# SI5324_CLK_RECOVERY.net
KiCad netlist of a schematic drawn in Altium Designer
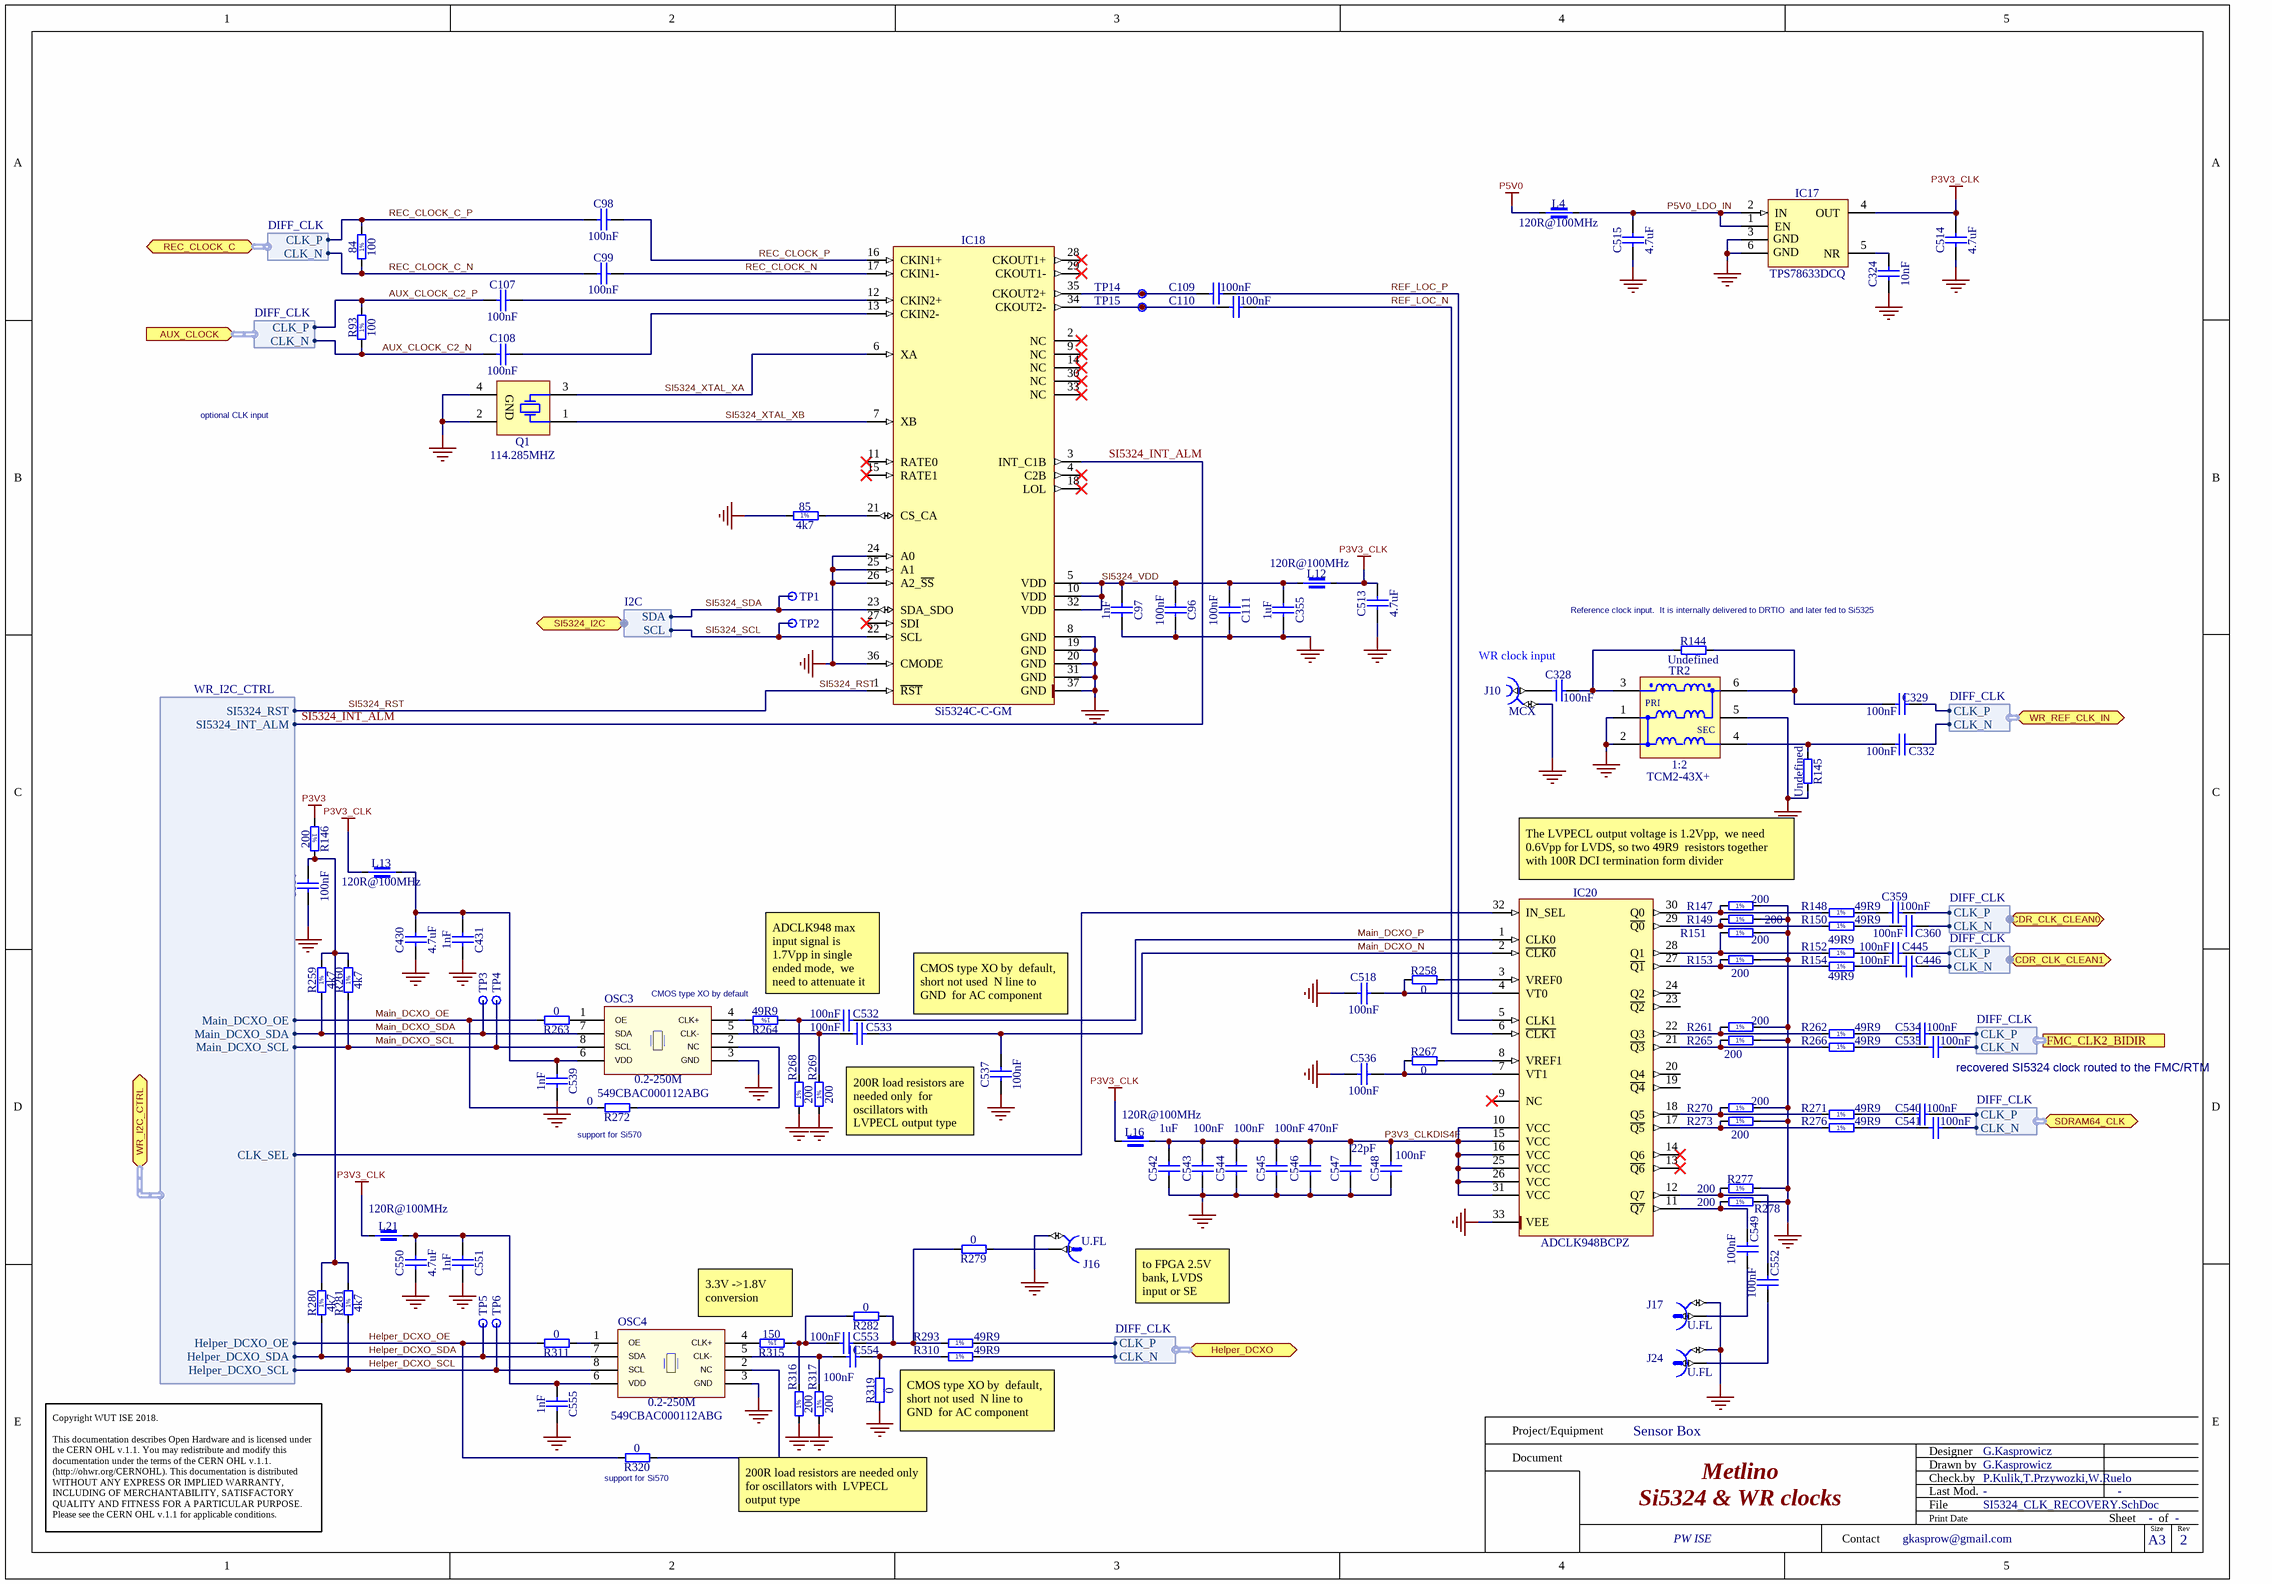
[diagram p0: SI5324_CLK_RECOVERY.SchDoc]

(export (version "E")
  (design (tool "Eeschema 10.0.6"))
  (components
    (comp (ref "84")
      (value "100")
      (footprint "RESC1005X40N")
      (description "Resistor - 1%")
      (fields
        (field (name "MANUFACTURER PART NUMBER") "R0402_100R_1%_0.0625W_100PPM")
        (field (name "MANUFACTURER") "GENERIC")
        (field (name "AUTHOR") "CERN DEM JLC")
      )
      (libsource (lib "Resistors") (part "Resistor - 1%"))
    )
    (comp (ref "85")
      (value "4k7")
      (footprint "RESC1005X40N")
      (description "Resistor - 1%")
      (fields
        (field (name "MANUFACTURER PART NUMBER") "R0402_4K7_1%_0.0625W_100PPM")
        (field (name "MANUFACTURER") "GENERIC")
        (field (name "AUTHOR") "CERN DEM JLC")
      )
      (libsource (lib "Resistors") (part "Resistor - 1%"))
    )
    (comp (ref "C96")
      (value "100nF")
      (footprint "CAPC0603X33N")
      (description "Non-polarised capacitor")
      (fields
        (field (name "MANUFACTURER PART NUMBER") "CC0201_100NF_6.3V_10%_X5R")
        (field (name "MANUFACTURER") "GENERIC")
        (field (name "AUTHOR") "CERN DEM JLC")
      )
      (libsource (lib "Capacitors") (part "Capacitor - non polarized"))
    )
    (comp (ref "C97")
      (value "1nF")
      (footprint "CAPC0603X33N")
      (description "Non-polarised capacitor")
      (fields
        (field (name "MANUFACTURER PART NUMBER") "CC0201_1NF_16V_10%_X5R")
        (field (name "MANUFACTURER") "GENERIC")
        (field (name "AUTHOR") "CERN DEM JLC")
      )
      (libsource (lib "Capacitors") (part "Capacitor - non polarized"))
    )
    (comp (ref "C98")
      (value "100nF")
      (footprint "CAPC0603X33N")
      (description "Non-polarised capacitor")
      (fields
        (field (name "MANUFACTURER PART NUMBER") "CC0201_100NF_6.3V_10%_X5R")
        (field (name "MANUFACTURER") "GENERIC")
        (field (name "AUTHOR") "CERN DEM JLC")
      )
      (libsource (lib "Capacitors") (part "Capacitor - non polarized"))
    )
    (comp (ref "C99")
      (value "100nF")
      (footprint "CAPC0603X33N")
      (description "Non-polarised capacitor")
      (fields
        (field (name "MANUFACTURER PART NUMBER") "CC0201_100NF_6.3V_10%_X5R")
        (field (name "MANUFACTURER") "GENERIC")
        (field (name "AUTHOR") "CERN DEM JLC")
      )
      (libsource (lib "Capacitors") (part "Capacitor - non polarized"))
    )
    (comp (ref "C107")
      (value "100nF")
      (footprint "CAPC0603X33N")
      (description "Non-polarised capacitor")
      (fields
        (field (name "MANUFACTURER PART NUMBER") "CC0201_100NF_6.3V_10%_X5R")
        (field (name "MANUFACTURER") "GENERIC")
        (field (name "AUTHOR") "CERN DEM JLC")
      )
      (libsource (lib "Capacitors") (part "Capacitor - non polarized"))
    )
    (comp (ref "C108")
      (value "100nF")
      (footprint "CAPC0603X33N")
      (description "Non-polarised capacitor")
      (fields
        (field (name "MANUFACTURER PART NUMBER") "CC0201_100NF_6.3V_10%_X5R")
        (field (name "MANUFACTURER") "GENERIC")
        (field (name "AUTHOR") "CERN DEM JLC")
      )
      (libsource (lib "Capacitors") (part "Capacitor - non polarized"))
    )
    (comp (ref "C109")
      (value "100nF")
      (footprint "CAPC1005X55N")
      (description "Non-polarised capacitor")
      (fields
        (field (name "MANUFACTURER PART NUMBER") "CC0402_100NF_16V_10%_X5R")
        (field (name "MANUFACTURER") "GENERIC")
        (field (name "AUTHOR") "CERN DEM JLC")
      )
      (libsource (lib "Capacitors") (part "Capacitor - non polarized"))
    )
    (comp (ref "C110")
      (value "100nF")
      (footprint "CAPC1005X55N")
      (description "Non-polarised capacitor")
      (fields
        (field (name "MANUFACTURER PART NUMBER") "CC0402_100NF_16V_10%_X5R")
        (field (name "MANUFACTURER") "GENERIC")
        (field (name "AUTHOR") "CERN DEM JLC")
      )
      (libsource (lib "Capacitors") (part "Capacitor - non polarized"))
    )
    (comp (ref "C111")
      (value "100nF")
      (footprint "CAPC0603X33N")
      (description "Non-polarised capacitor")
      (fields
        (field (name "MANUFACTURER PART NUMBER") "CC0201_100NF_6.3V_10%_X5R")
        (field (name "MANUFACTURER") "GENERIC")
        (field (name "AUTHOR") "CERN DEM JLC")
      )
      (libsource (lib "Capacitors") (part "Capacitor - non polarized"))
    )
    (comp (ref "C324")
      (value "10nF")
      (footprint "CAPC1608X87N")
      (description "Non-polarised capacitor")
      (fields
        (field (name "PART NUMBER") "CC0603_10NF_50V_5%_C0G")
        (field (name "VOLTAGE") "50V")
        (field (name "AUTHOR") "CERN DEM JLC")
      )
      (libsource (lib "Capacitors") (part "Capacitor - non polarized"))
    )
    (comp (ref "C328")
      (value "100nF")
      (footprint "CAPC1005X55N")
      (description "Non-polarised capacitor")
      (fields
        (field (name "MANUFACTURER PART NUMBER") "CC0402_100NF_16V_10%_X5R")
        (field (name "MANUFACTURER") "GENERIC")
        (field (name "AUTHOR") "CERN DEM JLC")
      )
      (libsource (lib "Capacitors") (part "Capacitor - non polarized"))
    )
    (comp (ref "C329")
      (value "100nF")
      (footprint "CAPC1005X55N")
      (description "Non-polarised capacitor")
      (fields
        (field (name "MANUFACTURER PART NUMBER") "CC0402_100NF_16V_10%_X5R")
        (field (name "MANUFACTURER") "GENERIC")
        (field (name "AUTHOR") "CERN DEM JLC")
      )
      (libsource (lib "Capacitors") (part "Capacitor - non polarized"))
    )
    (comp (ref "C332")
      (value "100nF")
      (footprint "CAPC1005X55N")
      (description "Non-polarised capacitor")
      (fields
        (field (name "MANUFACTURER PART NUMBER") "CC0402_100NF_16V_10%_X5R")
        (field (name "MANUFACTURER") "GENERIC")
        (field (name "AUTHOR") "CERN DEM JLC")
      )
      (libsource (lib "Capacitors") (part "Capacitor - non polarized"))
    )
    (comp (ref "C355")
      (value "1uF")
      (footprint "CAPC1005X55N")
      (description "Non-polarised capacitor")
      (fields
        (field (name "MANUFACTURER PART NUMBER") "CC0402_1UF_16V_10%_X5R")
        (field (name "MANUFACTURER") "GENERIC")
        (field (name "AUTHOR") "CERN DEM JLC")
      )
      (libsource (lib "Capacitors") (part "Capacitor - non polarized"))
    )
    (comp (ref "C356")
      (value "100nF")
      (footprint "CAPC0603X33N")
      (description "Non-polarised capacitor")
      (fields
        (field (name "MANUFACTURER PART NUMBER") "CC0201_100NF_6.3V_10%_X5R")
        (field (name "MANUFACTURER") "GENERIC")
        (field (name "AUTHOR") "CERN DEM JLC")
      )
      (libsource (lib "Capacitors") (part "Capacitor - non polarized"))
    )
    (comp (ref "C359")
      (value "100nF")
      (footprint "CAPC0603X33N")
      (description "Non-polarised capacitor")
      (fields
        (field (name "MANUFACTURER PART NUMBER") "CC0201_100NF_6.3V_10%_X5R")
        (field (name "MANUFACTURER") "GENERIC")
        (field (name "AUTHOR") "CERN DEM JLC")
      )
      (libsource (lib "Capacitors") (part "Capacitor - non polarized"))
    )
    (comp (ref "C360")
      (value "100nF")
      (footprint "CAPC0603X33N")
      (description "Non-polarised capacitor")
      (fields
        (field (name "MANUFACTURER PART NUMBER") "CC0201_100NF_6.3V_10%_X5R")
        (field (name "MANUFACTURER") "GENERIC")
        (field (name "AUTHOR") "CERN DEM JLC")
      )
      (libsource (lib "Capacitors") (part "Capacitor - non polarized"))
    )
    (comp (ref "C430")
      (value "4.7uF")
      (footprint "CAPC1608X90N")
      (description "Non-polarised capacitor")
      (fields
        (field (name "MANUFACTURER PART NUMBER") "CC0603_4.7UF_25V_10%_X5R")
        (field (name "MANUFACTURER") "GENERIC")
        (field (name "AUTHOR") "CERN DEM JLC")
      )
      (libsource (lib "Capacitors") (part "Capacitor - non polarized"))
    )
    (comp (ref "C431")
      (value "1nF")
      (footprint "CAPC0603X33N")
      (description "Non-polarised capacitor")
      (fields
        (field (name "MANUFACTURER PART NUMBER") "CC0201_1NF_16V_10%_X5R")
        (field (name "MANUFACTURER") "GENERIC")
        (field (name "AUTHOR") "CERN DEM JLC")
      )
      (libsource (lib "Capacitors") (part "Capacitor - non polarized"))
    )
    (comp (ref "C445")
      (value "100nF")
      (footprint "CAPC0603X33N")
      (description "Non-polarised capacitor")
      (fields
        (field (name "MANUFACTURER PART NUMBER") "CC0201_100NF_6.3V_10%_X5R")
        (field (name "MANUFACTURER") "GENERIC")
        (field (name "AUTHOR") "CERN DEM JLC")
      )
      (libsource (lib "Capacitors") (part "Capacitor - non polarized"))
    )
    (comp (ref "C446")
      (value "100nF")
      (footprint "CAPC0603X33N")
      (description "Non-polarised capacitor")
      (fields
        (field (name "MANUFACTURER PART NUMBER") "CC0201_100NF_6.3V_10%_X5R")
        (field (name "MANUFACTURER") "GENERIC")
        (field (name "AUTHOR") "CERN DEM JLC")
      )
      (libsource (lib "Capacitors") (part "Capacitor - non polarized"))
    )
    (comp (ref "C513")
      (value "4.7uF")
      (footprint "CAPC1608X90N")
      (description "Non-polarised capacitor")
      (fields
        (field (name "MANUFACTURER PART NUMBER") "CC0603_4.7UF_25V_10%_X5R")
        (field (name "MANUFACTURER") "GENERIC")
        (field (name "AUTHOR") "CERN DEM JLC")
      )
      (libsource (lib "Capacitors") (part "Capacitor - non polarized"))
    )
    (comp (ref "C514")
      (value "4.7uF")
      (footprint "CAPC1608X90N")
      (description "Non-polarised capacitor")
      (fields
        (field (name "MANUFACTURER PART NUMBER") "CC0603_4.7UF_25V_10%_X5R")
        (field (name "MANUFACTURER") "GENERIC")
        (field (name "AUTHOR") "CERN DEM JLC")
      )
      (libsource (lib "Capacitors") (part "Capacitor - non polarized"))
    )
    (comp (ref "C515")
      (value "4.7uF")
      (footprint "CAPC1608X90N")
      (description "Non-polarised capacitor")
      (fields
        (field (name "MANUFACTURER PART NUMBER") "CC0603_4.7UF_25V_10%_X5R")
        (field (name "MANUFACTURER") "GENERIC")
        (field (name "AUTHOR") "CERN DEM JLC")
      )
      (libsource (lib "Capacitors") (part "Capacitor - non polarized"))
    )
    (comp (ref "C518")
      (value "100nF")
      (footprint "CAPC0603X33N")
      (description "Non-polarised capacitor")
      (fields
        (field (name "MANUFACTURER PART NUMBER") "CC0201_100NF_6.3V_10%_X5R")
        (field (name "MANUFACTURER") "GENERIC")
        (field (name "AUTHOR") "CERN DEM JLC")
      )
      (libsource (lib "Capacitors") (part "Capacitor - non polarized"))
    )
    (comp (ref "C532")
      (value "100nF")
      (footprint "CAPC1005X55N")
      (description "Non-polarised capacitor")
      (fields
        (field (name "MANUFACTURER PART NUMBER") "CC0402_100NF_16V_10%_X5R")
        (field (name "MANUFACTURER") "GENERIC")
        (field (name "AUTHOR") "CERN DEM JLC")
      )
      (libsource (lib "Capacitors") (part "Capacitor - non polarized"))
    )
    (comp (ref "C533")
      (value "100nF")
      (footprint "CAPC1005X55N")
      (description "Non-polarised capacitor")
      (fields
        (field (name "MANUFACTURER PART NUMBER") "CC0402_100NF_16V_10%_X5R")
        (field (name "MANUFACTURER") "GENERIC")
        (field (name "AUTHOR") "CERN DEM JLC")
      )
      (libsource (lib "Capacitors") (part "Capacitor - non polarized"))
    )
    (comp (ref "C534")
      (value "100nF")
      (footprint "CAPC0603X33N")
      (description "Non-polarised capacitor")
      (fields
        (field (name "MANUFACTURER PART NUMBER") "CC0201_100NF_6.3V_10%_X5R")
        (field (name "MANUFACTURER") "GENERIC")
        (field (name "AUTHOR") "CERN DEM JLC")
      )
      (libsource (lib "Capacitors") (part "Capacitor - non polarized"))
    )
    (comp (ref "C535")
      (value "100nF")
      (footprint "CAPC0603X33N")
      (description "Non-polarised capacitor")
      (fields
        (field (name "MANUFACTURER PART NUMBER") "CC0201_100NF_6.3V_10%_X5R")
        (field (name "MANUFACTURER") "GENERIC")
        (field (name "AUTHOR") "CERN DEM JLC")
      )
      (libsource (lib "Capacitors") (part "Capacitor - non polarized"))
    )
    (comp (ref "C536")
      (value "100nF")
      (footprint "CAPC0603X33N")
      (description "Non-polarised capacitor")
      (fields
        (field (name "MANUFACTURER PART NUMBER") "CC0201_100NF_6.3V_10%_X5R")
        (field (name "MANUFACTURER") "GENERIC")
        (field (name "AUTHOR") "CERN DEM JLC")
      )
      (libsource (lib "Capacitors") (part "Capacitor - non polarized"))
    )
    (comp (ref "C537")
      (value "100nF")
      (footprint "CAPC0603X33N")
      (description "Non-polarised capacitor")
      (fields
        (field (name "MANUFACTURER PART NUMBER") "CC0201_100NF_6.3V_10%_X5R")
        (field (name "MANUFACTURER") "GENERIC")
        (field (name "AUTHOR") "CERN DEM JLC")
      )
      (libsource (lib "Capacitors") (part "Capacitor - non polarized"))
    )
    (comp (ref "C539")
      (value "1nF")
      (footprint "CAPC0603X33N")
      (description "Non-polarised capacitor")
      (fields
        (field (name "MANUFACTURER PART NUMBER") "CC0201_1NF_16V_10%_X5R")
        (field (name "MANUFACTURER") "GENERIC")
        (field (name "AUTHOR") "CERN DEM JLC")
      )
      (libsource (lib "Capacitors") (part "Capacitor - non polarized"))
    )
    (comp (ref "C540")
      (value "100nF")
      (footprint "CAPC0603X33N")
      (description "Non-polarised capacitor")
      (fields
        (field (name "MANUFACTURER PART NUMBER") "CC0201_100NF_6.3V_10%_X5R")
        (field (name "MANUFACTURER") "GENERIC")
        (field (name "AUTHOR") "CERN DEM JLC")
      )
      (libsource (lib "Capacitors") (part "Capacitor - non polarized"))
    )
    (comp (ref "C541")
      (value "100nF")
      (footprint "CAPC0603X33N")
      (description "Non-polarised capacitor")
      (fields
        (field (name "MANUFACTURER PART NUMBER") "CC0201_100NF_6.3V_10%_X5R")
        (field (name "MANUFACTURER") "GENERIC")
        (field (name "AUTHOR") "CERN DEM JLC")
      )
      (libsource (lib "Capacitors") (part "Capacitor - non polarized"))
    )
    (comp (ref "C542")
      (value "1uF")
      (footprint "CAPC1005X55N")
      (description "Non-polarised capacitor")
      (fields
        (field (name "MANUFACTURER PART NUMBER") "CC0402_1UF_16V_10%_X5R")
        (field (name "MANUFACTURER") "GENERIC")
        (field (name "AUTHOR") "CERN DEM JLC")
      )
      (libsource (lib "Capacitors") (part "Capacitor - non polarized"))
    )
    (comp (ref "C543")
      (value "100nF")
      (footprint "CAPC0603X33N")
      (description "Non-polarised capacitor")
      (fields
        (field (name "MANUFACTURER PART NUMBER") "CC0201_100NF_6.3V_10%_X5R")
        (field (name "MANUFACTURER") "GENERIC")
        (field (name "AUTHOR") "CERN DEM JLC")
      )
      (libsource (lib "Capacitors") (part "Capacitor - non polarized"))
    )
    (comp (ref "C544")
      (value "100nF")
      (footprint "CAPC0603X33N")
      (description "Non-polarised capacitor")
      (fields
        (field (name "MANUFACTURER PART NUMBER") "CC0201_100NF_6.3V_10%_X5R")
        (field (name "MANUFACTURER") "GENERIC")
        (field (name "AUTHOR") "CERN DEM JLC")
      )
      (libsource (lib "Capacitors") (part "Capacitor - non polarized"))
    )
    (comp (ref "C545")
      (value "100nF")
      (footprint "CAPC0603X33N")
      (description "Non-polarised capacitor")
      (fields
        (field (name "MANUFACTURER PART NUMBER") "CC0201_100NF_6.3V_10%_X5R")
        (field (name "MANUFACTURER") "GENERIC")
        (field (name "AUTHOR") "CERN DEM JLC")
      )
      (libsource (lib "Capacitors") (part "Capacitor - non polarized"))
    )
    (comp (ref "C546")
      (value "470nF")
      (footprint "CAPC1005X55N")
      (description "Non-polarised capacitor")
      (fields
        (field (name "MANUFACTURER PART NUMBER") "CC0402_470NF_16V_10%_X5R")
        (field (name "MANUFACTURER") "GENERIC")
        (field (name "AUTHOR") "CERN DEM JLC")
      )
      (libsource (lib "Capacitors") (part "Capacitor - non polarized"))
    )
    (comp (ref "C547")
      (value "22pF")
      (footprint "CAPC1005X55N")
      (description "Non-polarised capacitor")
      (fields
        (field (name "MANUFACTURER PART NUMBER") "CC0402_22PF_50V_5%_C0G")
        (field (name "MANUFACTURER") "GENERIC")
        (field (name "AUTHOR") "CERN DEM JLC")
      )
      (libsource (lib "Capacitors") (part "Capacitor - non polarized"))
    )
    (comp (ref "C548")
      (value "100nF")
      (footprint "CAPC0603X33N")
      (description "Non-polarised capacitor")
      (fields
        (field (name "MANUFACTURER PART NUMBER") "CC0201_100NF_6.3V_10%_X5R")
        (field (name "MANUFACTURER") "GENERIC")
        (field (name "AUTHOR") "CERN DEM JLC")
      )
      (libsource (lib "Capacitors") (part "Capacitor - non polarized"))
    )
    (comp (ref "C549")
      (value "100nF")
      (footprint "CAPC0603X33N")
      (description "Non-polarised capacitor")
      (fields
        (field (name "MANUFACTURER PART NUMBER") "CC0201_100NF_6.3V_10%_X5R")
        (field (name "MANUFACTURER") "GENERIC")
        (field (name "AUTHOR") "CERN DEM JLC")
      )
      (libsource (lib "Capacitors") (part "Capacitor - non polarized"))
    )
    (comp (ref "C550")
      (value "4.7uF")
      (footprint "CAPC1608X90N")
      (description "Non-polarised capacitor")
      (fields
        (field (name "MANUFACTURER PART NUMBER") "CC0603_4.7UF_25V_10%_X5R")
        (field (name "MANUFACTURER") "GENERIC")
        (field (name "AUTHOR") "CERN DEM JLC")
      )
      (libsource (lib "Capacitors") (part "Capacitor - non polarized"))
    )
    (comp (ref "C551")
      (value "1nF")
      (footprint "CAPC0603X33N")
      (description "Non-polarised capacitor")
      (fields
        (field (name "MANUFACTURER PART NUMBER") "CC0201_1NF_16V_10%_X5R")
        (field (name "MANUFACTURER") "GENERIC")
        (field (name "AUTHOR") "CERN DEM JLC")
      )
      (libsource (lib "Capacitors") (part "Capacitor - non polarized"))
    )
    (comp (ref "C552")
      (value "100nF")
      (footprint "CAPC0603X33N")
      (description "Non-polarised capacitor")
      (fields
        (field (name "MANUFACTURER PART NUMBER") "CC0201_100NF_6.3V_10%_X5R")
        (field (name "MANUFACTURER") "GENERIC")
        (field (name "AUTHOR") "CERN DEM JLC")
      )
      (libsource (lib "Capacitors") (part "Capacitor - non polarized"))
    )
    (comp (ref "C553")
      (value "100nF")
      (footprint "CAPC1005X55N")
      (description "Non-polarised capacitor")
      (fields
        (field (name "MANUFACTURER PART NUMBER") "CC0402_100NF_16V_10%_X5R")
        (field (name "MANUFACTURER") "GENERIC")
        (field (name "AUTHOR") "CERN DEM JLC")
      )
      (libsource (lib "Capacitors") (part "Capacitor - non polarized"))
    )
    (comp (ref "C554")
      (value "100nF")
      (footprint "CAPC1005X55N")
      (description "Non-polarised capacitor")
      (fields
        (field (name "MANUFACTURER PART NUMBER") "CC0402_100NF_16V_10%_X5R")
        (field (name "MANUFACTURER") "GENERIC")
        (field (name "AUTHOR") "CERN DEM JLC")
      )
      (libsource (lib "Capacitors") (part "Capacitor - non polarized"))
    )
    (comp (ref "C555")
      (value "1nF")
      (footprint "CAPC0603X33N")
      (description "Non-polarised capacitor")
      (fields
        (field (name "MANUFACTURER PART NUMBER") "CC0201_1NF_16V_10%_X5R")
        (field (name "MANUFACTURER") "GENERIC")
        (field (name "AUTHOR") "CERN DEM JLC")
      )
      (libsource (lib "Capacitors") (part "Capacitor - non polarized"))
    )
    (comp (ref "IC17")
      (value "TPS78633DCQ")
      (footprint "SOT127P700X180-6N")
      (description "Ultralow-Noise, High-PSRR, Fast, RF, 1.5A Low-Dropout Linear Regulator")
      (fields (field (name "MANUFACTURER") "TEXAS INSTRUMENTS") (field (name "AUTHOR") "CERN DEM JMW"))
      (libsource (lib "ICs And Semiconductors") (part "TPS786xxDCQ"))
    )
    (comp (ref "IC18")
      (value "Si5324C-C-GM")
      (footprint "QFN50P600X600X90-37N-S425")
      (description "Any Frequency Precision Clock Multiplier/Jitter Attenuator")
      (fields (field (name "MANUFACTURER") "SILICON LABS") (field (name "AUTHOR") "CERN DEM JLC"))
      (libsource (lib "ICs And Semiconductors") (part "Si5324"))
    )
    (comp (ref "IC20")
      (value "ADCLK948BCPZ")
      (footprint "QFN50P500X500X80-33N-S285")
      (description "Two Selectable Inputs, 8 LVPECL Outputs, SiGe Clock Fanout Buffer")
      (fields (field (name "MANUFACTURER") "ANALOG DEVICES") (field (name "AUTHOR") "CERN DEM MR"))
      (libsource (lib "ICs And Semiconductors") (part "ADCLK948"))
    )
    (comp (ref "J10")
      (value "MCX")
      (footprint "AMPHENOL_ARF2521-ND")
      (fields
        (field (name "PART NUMBER") "AMPHENOL_ARF2521-ND")
        (field (name "MANUFACTURER") "AMPHENOL")
        (field (name "AUTHOR") "GK")
      )
      (libsource (lib "LIBRARY_SCH") (part "CON_MCX"))
    )
    (comp (ref "J16")
      (value "U.FL")
      (footprint "HIROSE_U.FL-R-SMT-1(10)")
      (fields
        (field (name "MANUFACTURER PART NUMBER") "U.FL-R-SMT-1(10)")
        (field (name "MANUFACTURER") "HIROSE (HRS)")
        (field (name "PART NUMBER") "HIROSE_U.FL-R-SMT-1(10)")
        (field (name "AUTHOR") "CERN DEM JLC")
      )
      (libsource (lib "") (part "Coax_1Male_1Shield_1"))
    )
    (comp (ref "J17")
      (value "U.FL")
      (footprint "HIROSE_U.FL-R-SMT-1(10)")
      (fields
        (field (name "MANUFACTURER PART NUMBER") "U.FL-R-SMT-1(10)")
        (field (name "MANUFACTURER") "HIROSE (HRS)")
        (field (name "PART NUMBER") "HIROSE_U.FL-R-SMT-1(10)")
        (field (name "AUTHOR") "CERN DEM JLC")
      )
      (libsource (lib "Connectors") (part "Coax_1Male_1Shield"))
    )
    (comp (ref "J24")
      (value "U.FL")
      (footprint "HIROSE_U.FL-R-SMT-1(10)")
      (fields
        (field (name "MANUFACTURER PART NUMBER") "U.FL-R-SMT-1(10)")
        (field (name "MANUFACTURER") "HIROSE (HRS)")
        (field (name "PART NUMBER") "HIROSE_U.FL-R-SMT-1(10)")
        (field (name "AUTHOR") "CERN DEM JLC")
      )
      (libsource (lib "Connectors") (part "Coax_1Male_1Shield"))
    )
    (comp (ref "L4")
      (value "120R@100MHz")
      (footprint "INDC1608X95N")
      (fields
        (field (name "MANUFACTURER PART NUMBER") "BLM18PG121SN1D")
        (field (name "MANUFACTURER") "MURATA")
        (field (name "PART NUMBER") "IND0603_MURATA_BLM18PG121SN1D")
        (field (name "AUTHOR") "CERN DEM BC")
      )
      (libsource (lib "Inductors & Transformers") (part "Ferrite Bead"))
    )
    (comp (ref "L12")
      (value "120R@100MHz")
      (footprint "INDC1608X95N")
      (fields
        (field (name "MANUFACTURER PART NUMBER") "BLM18PG121SN1D")
        (field (name "MANUFACTURER") "MURATA")
        (field (name "PART NUMBER") "IND0603_MURATA_BLM18PG121SN1D")
        (field (name "AUTHOR") "CERN DEM BC")
      )
      (libsource (lib "") (part "Ferrite Bead_1"))
    )
    (comp (ref "L13")
      (value "120R@100MHz")
      (footprint "INDC1608X95N")
      (fields
        (field (name "MANUFACTURER PART NUMBER") "BLM18PG121SN1D")
        (field (name "MANUFACTURER") "MURATA")
        (field (name "PART NUMBER") "IND0603_MURATA_BLM18PG121SN1D")
        (field (name "AUTHOR") "CERN DEM BC")
      )
      (libsource (lib "Inductors & Transformers") (part "Ferrite Bead"))
    )
    (comp (ref "L16")
      (value "120R@100MHz")
      (footprint "INDC1608X95N")
      (fields
        (field (name "MANUFACTURER PART NUMBER") "BLM18PG121SN1D")
        (field (name "MANUFACTURER") "MURATA")
        (field (name "PART NUMBER") "IND0603_MURATA_BLM18PG121SN1D")
        (field (name "AUTHOR") "CERN DEM BC")
      )
      (libsource (lib "Inductors & Transformers") (part "Ferrite Bead"))
    )
    (comp (ref "L21")
      (value "120R@100MHz")
      (footprint "INDC1608X95N")
      (fields
        (field (name "MANUFACTURER PART NUMBER") "BLM18PG121SN1D")
        (field (name "MANUFACTURER") "MURATA")
        (field (name "PART NUMBER") "IND0603_MURATA_BLM18PG121SN1D")
        (field (name "AUTHOR") "CERN DEM BC")
      )
      (libsource (lib "Inductors & Transformers") (part "Ferrite Bead"))
    )
    (comp (ref "OSC3")
      (value "0.2-250M")
      (footprint "OSC_SILICON-LAB_SI549")
      (fields
        (field (name "MANUFACTURER PART NUMBER") "549CBAC000112ABG")
        (field (name "MANUFACTURER") "Silabs")
        (field (name "PART NUMBER") "OSC_0.2_250M_SILICON-LAB_549CBAC000112ABG")
      )
      (libsource (lib "LIBRARY_SCH") (part "OSC_SILICON-LAB_SI549"))
    )
    (comp (ref "OSC4")
      (value "0.2-250M")
      (footprint "OSC_SILICON-LAB_SI549")
      (fields
        (field (name "MANUFACTURER PART NUMBER") "549CBAC000112ABG")
        (field (name "MANUFACTURER") "Silabs")
        (field (name "PART NUMBER") "OSC_0.2_250M_SILICON-LAB_549CBAC000112ABG")
      )
      (libsource (lib "LIBRARY_SCH") (part "OSC_SILICON-LAB_SI549"))
    )
    (comp (ref "Q1")
      (value "114.285MHZ")
      (footprint "XTAL_CONNOR_CS")
      (description "Crystal 4 pins 1=XTAL Control 2=GND3=XTAL 4=GND")
      (fields
        (field (name "MANUFACTURER PART NUMBER") "CS-023-114.285M")
        (field (name "MANUFACTURER") "CONNOR-WINFIELD")
        (field (name "AUTHOR") "CERN DEM JLC")
      )
      (libsource (lib "ICs And Semiconductors") (part "Quartz Crystal 1X 2GND 3X 4GND"))
    )
    (comp (ref "R93")
      (value "100")
      (footprint "RESC1005X40N")
      (description "Resistor - 1%")
      (fields
        (field (name "MANUFACTURER PART NUMBER") "R0402_100R_1%_0.0625W_100PPM")
        (field (name "MANUFACTURER") "GENERIC")
        (field (name "AUTHOR") "CERN DEM JLC")
      )
      (libsource (lib "Resistors") (part "Resistor - 1%"))
    )
    (comp (ref "R144")
      (value "Undefined")
      (footprint "RESC1005X40N")
      (description "Resistor")
      (fields
        (field (name "MANUFACTURER PART NUMBER") "R0402_NO-VALUE")
        (field (name "AUTHOR") "CERN DEM JLC")
      )
      (libsource (lib "Resistors") (part "Resistor"))
    )
    (comp (ref "R145")
      (value "Undefined")
      (footprint "RESC1005X40N")
      (description "Resistor")
      (fields
        (field (name "MANUFACTURER PART NUMBER") "R0402_NO-VALUE")
        (field (name "AUTHOR") "CERN DEM JLC")
      )
      (libsource (lib "Resistors") (part "Resistor"))
    )
    (comp (ref "R146")
      (value "200")
      (footprint "RESC1005X40N")
      (description "Resistor - 1%")
      (fields
        (field (name "MANUFACTURER PART NUMBER") "R0402_200R_1%_0.0625W_100PPM")
        (field (name "MANUFACTURER") "GENERIC")
        (field (name "AUTHOR") "CERN DEM JLC")
      )
      (libsource (lib "Resistors") (part "Resistor - 1%"))
    )
    (comp (ref "R147")
      (value "200")
      (footprint "RESC1005X40N")
      (description "Resistor - 1%")
      (fields
        (field (name "MANUFACTURER PART NUMBER") "R0402_200R_1%_0.0625W_100PPM")
        (field (name "MANUFACTURER") "GENERIC")
        (field (name "AUTHOR") "CERN DEM JLC")
      )
      (libsource (lib "Resistors") (part "Resistor - 1%"))
    )
    (comp (ref "R148")
      (value "49R9")
      (footprint "RESC1005X40N")
      (description "Resistor - 1%")
      (fields
        (field (name "MANUFACTURER PART NUMBER") "R0402_49R9_1%_0.0625W_100PPM")
        (field (name "MANUFACTURER") "GENERIC")
        (field (name "AUTHOR") "CERN DEM JLC")
      )
      (libsource (lib "Resistors") (part "Resistor - 1%"))
    )
    (comp (ref "R149")
      (value "200")
      (footprint "RESC1005X40N")
      (description "Resistor - 1%")
      (fields
        (field (name "MANUFACTURER PART NUMBER") "R0402_200R_1%_0.0625W_100PPM")
        (field (name "MANUFACTURER") "GENERIC")
        (field (name "AUTHOR") "CERN DEM JLC")
      )
      (libsource (lib "Resistors") (part "Resistor - 1%"))
    )
    (comp (ref "R150")
      (value "49R9")
      (footprint "RESC1005X40N")
      (description "Resistor - 1%")
      (fields
        (field (name "MANUFACTURER PART NUMBER") "R0402_49R9_1%_0.0625W_100PPM")
        (field (name "MANUFACTURER") "GENERIC")
        (field (name "AUTHOR") "CERN DEM JLC")
      )
      (libsource (lib "Resistors") (part "Resistor - 1%"))
    )
    (comp (ref "R151")
      (value "200")
      (footprint "RESC1005X40N")
      (description "Resistor - 1%")
      (fields
        (field (name "MANUFACTURER PART NUMBER") "R0402_200R_1%_0.0625W_100PPM")
        (field (name "MANUFACTURER") "GENERIC")
        (field (name "AUTHOR") "CERN DEM JLC")
      )
      (libsource (lib "Resistors") (part "Resistor - 1%"))
    )
    (comp (ref "R152")
      (value "49R9")
      (footprint "RESC1005X40N")
      (description "Resistor - 1%")
      (fields
        (field (name "MANUFACTURER PART NUMBER") "R0402_49R9_1%_0.0625W_100PPM")
        (field (name "MANUFACTURER") "GENERIC")
        (field (name "AUTHOR") "CERN DEM JLC")
      )
      (libsource (lib "Resistors") (part "Resistor - 1%"))
    )
    (comp (ref "R153")
      (value "200")
      (footprint "RESC1005X40N")
      (description "Resistor - 1%")
      (fields
        (field (name "MANUFACTURER PART NUMBER") "R0402_200R_1%_0.0625W_100PPM")
        (field (name "MANUFACTURER") "GENERIC")
        (field (name "AUTHOR") "CERN DEM JLC")
      )
      (libsource (lib "Resistors") (part "Resistor - 1%"))
    )
    (comp (ref "R154")
      (value "49R9")
      (footprint "RESC1005X40N")
      (description "Resistor - 1%")
      (fields
        (field (name "MANUFACTURER PART NUMBER") "R0402_49R9_1%_0.0625W_100PPM")
        (field (name "MANUFACTURER") "GENERIC")
        (field (name "AUTHOR") "CERN DEM JLC")
      )
      (libsource (lib "Resistors") (part "Resistor - 1%"))
    )
    (comp (ref "R258")
      (value "0")
      (footprint "RESC1005X40N")
      (description "Resistor")
      (fields
        (field (name "MANUFACTURER PART NUMBER") "R0402_0R_JUMPER")
        (field (name "MANUFACTURER") "GENERIC")
        (field (name "AUTHOR") "CERN DEM JLC")
      )
      (libsource (lib "Resistors") (part "Resistor"))
    )
    (comp (ref "R259")
      (value "4k7")
      (footprint "RESC1005X40N")
      (description "Resistor - 1%")
      (fields
        (field (name "MANUFACTURER PART NUMBER") "R0402_4K7_1%_0.0625W_100PPM")
        (field (name "MANUFACTURER") "GENERIC")
        (field (name "AUTHOR") "CERN DEM JLC")
      )
      (libsource (lib "Resistors") (part "Resistor - 1%"))
    )
    (comp (ref "R260")
      (value "4k7")
      (footprint "RESC1005X40N")
      (description "Resistor - 1%")
      (fields
        (field (name "MANUFACTURER PART NUMBER") "R0402_4K7_1%_0.0625W_100PPM")
        (field (name "MANUFACTURER") "GENERIC")
        (field (name "AUTHOR") "CERN DEM JLC")
      )
      (libsource (lib "Resistors") (part "Resistor - 1%"))
    )
    (comp (ref "R261")
      (value "200")
      (footprint "RESC1005X40N")
      (description "Resistor - 1%")
      (fields
        (field (name "MANUFACTURER PART NUMBER") "R0402_200R_1%_0.0625W_100PPM")
        (field (name "MANUFACTURER") "GENERIC")
        (field (name "AUTHOR") "CERN DEM JLC")
      )
      (libsource (lib "Resistors") (part "Resistor - 1%"))
    )
    (comp (ref "R262")
      (value "49R9")
      (footprint "RESC1005X40N")
      (description "Resistor - 1%")
      (fields
        (field (name "MANUFACTURER PART NUMBER") "R0402_49R9_1%_0.0625W_100PPM")
        (field (name "MANUFACTURER") "GENERIC")
        (field (name "AUTHOR") "CERN DEM JLC")
      )
      (libsource (lib "Resistors") (part "Resistor - 1%"))
    )
    (comp (ref "R263")
      (value "0")
      (footprint "RESC1005X40N")
      (description "Resistor")
      (fields
        (field (name "MANUFACTURER PART NUMBER") "R0402_0R_JUMPER")
        (field (name "MANUFACTURER") "GENERIC")
        (field (name "AUTHOR") "CERN DEM JLC")
      )
      (libsource (lib "Resistors") (part "Resistor"))
    )
    (comp (ref "R264")
      (value "49R9")
      (footprint "RESC1005X40N")
      (description "Resistor - 1%")
      (fields
        (field (name "MANUFACTURER PART NUMBER") "R0402_49R9_1%_0.0625W_100PPM")
        (field (name "MANUFACTURER") "GENERIC")
        (field (name "AUTHOR") "CERN DEM JLC")
      )
      (libsource (lib "Resistors") (part "Resistor - 1%"))
    )
    (comp (ref "R265")
      (value "200")
      (footprint "RESC1005X40N")
      (description "Resistor - 1%")
      (fields
        (field (name "MANUFACTURER PART NUMBER") "R0402_200R_1%_0.0625W_100PPM")
        (field (name "MANUFACTURER") "GENERIC")
        (field (name "AUTHOR") "CERN DEM JLC")
      )
      (libsource (lib "Resistors") (part "Resistor - 1%"))
    )
    (comp (ref "R266")
      (value "49R9")
      (footprint "RESC1005X40N")
      (description "Resistor - 1%")
      (fields
        (field (name "MANUFACTURER PART NUMBER") "R0402_49R9_1%_0.0625W_100PPM")
        (field (name "MANUFACTURER") "GENERIC")
        (field (name "AUTHOR") "CERN DEM JLC")
      )
      (libsource (lib "Resistors") (part "Resistor - 1%"))
    )
    (comp (ref "R267")
      (value "0")
      (footprint "RESC1005X40N")
      (description "Resistor")
      (fields
        (field (name "MANUFACTURER PART NUMBER") "R0402_0R_JUMPER")
        (field (name "MANUFACTURER") "GENERIC")
        (field (name "AUTHOR") "CERN DEM JLC")
      )
      (libsource (lib "Resistors") (part "Resistor"))
    )
    (comp (ref "R268")
      (value "200")
      (footprint "RESC1005X40N")
      (description "Resistor - 1%")
      (fields
        (field (name "MANUFACTURER PART NUMBER") "R0402_200R_1%_0.0625W_100PPM")
        (field (name "MANUFACTURER") "GENERIC")
        (field (name "AUTHOR") "CERN DEM JLC")
      )
      (libsource (lib "Resistors") (part "Resistor - 1%"))
    )
    (comp (ref "R269")
      (value "200")
      (footprint "RESC1005X40N")
      (description "Resistor - 1%")
      (fields
        (field (name "MANUFACTURER PART NUMBER") "R0402_200R_1%_0.0625W_100PPM")
        (field (name "MANUFACTURER") "GENERIC")
        (field (name "AUTHOR") "CERN DEM JLC")
      )
      (libsource (lib "Resistors") (part "Resistor - 1%"))
    )
    (comp (ref "R270")
      (value "200")
      (footprint "RESC1005X40N")
      (description "Resistor - 1%")
      (fields
        (field (name "MANUFACTURER PART NUMBER") "R0402_200R_1%_0.0625W_100PPM")
        (field (name "MANUFACTURER") "GENERIC")
        (field (name "AUTHOR") "CERN DEM JLC")
      )
      (libsource (lib "Resistors") (part "Resistor - 1%"))
    )
    (comp (ref "R271")
      (value "49R9")
      (footprint "RESC1005X40N")
      (description "Resistor - 1%")
      (fields
        (field (name "MANUFACTURER PART NUMBER") "R0402_49R9_1%_0.0625W_100PPM")
        (field (name "MANUFACTURER") "GENERIC")
        (field (name "AUTHOR") "CERN DEM JLC")
      )
      (libsource (lib "Resistors") (part "Resistor - 1%"))
    )
    (comp (ref "R272")
      (value "0")
      (footprint "RESC1005X40N")
      (description "Resistor")
      (fields
        (field (name "MANUFACTURER PART NUMBER") "R0402_0R_JUMPER")
        (field (name "MANUFACTURER") "GENERIC")
        (field (name "AUTHOR") "CERN DEM JLC")
      )
      (libsource (lib "Resistors") (part "Resistor"))
    )
    (comp (ref "R273")
      (value "200")
      (footprint "RESC1005X40N")
      (description "Resistor - 1%")
      (fields
        (field (name "MANUFACTURER PART NUMBER") "R0402_200R_1%_0.0625W_100PPM")
        (field (name "MANUFACTURER") "GENERIC")
        (field (name "AUTHOR") "CERN DEM JLC")
      )
      (libsource (lib "Resistors") (part "Resistor - 1%"))
    )
    (comp (ref "R276")
      (value "49R9")
      (footprint "RESC1005X40N")
      (description "Resistor - 1%")
      (fields
        (field (name "MANUFACTURER PART NUMBER") "R0402_49R9_1%_0.0625W_100PPM")
        (field (name "MANUFACTURER") "GENERIC")
        (field (name "AUTHOR") "CERN DEM JLC")
      )
      (libsource (lib "Resistors") (part "Resistor - 1%"))
    )
    (comp (ref "R277")
      (value "200")
      (footprint "RESC1005X40N")
      (description "Resistor - 1%")
      (fields
        (field (name "MANUFACTURER PART NUMBER") "R0402_200R_1%_0.0625W_100PPM")
        (field (name "MANUFACTURER") "GENERIC")
        (field (name "AUTHOR") "CERN DEM JLC")
      )
      (libsource (lib "Resistors") (part "Resistor - 1%"))
    )
    (comp (ref "R278")
      (value "200")
      (footprint "RESC1005X40N")
      (description "Resistor - 1%")
      (fields
        (field (name "MANUFACTURER PART NUMBER") "R0402_200R_1%_0.0625W_100PPM")
        (field (name "MANUFACTURER") "GENERIC")
        (field (name "AUTHOR") "CERN DEM JLC")
      )
      (libsource (lib "Resistors") (part "Resistor - 1%"))
    )
    (comp (ref "R279")
      (value "0")
      (footprint "RESC1005X40N")
      (description "Resistor")
      (fields
        (field (name "MANUFACTURER PART NUMBER") "R0402_0R_JUMPER")
        (field (name "MANUFACTURER") "GENERIC")
        (field (name "AUTHOR") "CERN DEM JLC")
      )
      (libsource (lib "Resistors") (part "Resistor"))
    )
    (comp (ref "R280")
      (value "4k7")
      (footprint "RESC1005X40N")
      (description "Resistor - 1%")
      (fields
        (field (name "MANUFACTURER PART NUMBER") "R0402_4K7_1%_0.0625W_100PPM")
        (field (name "MANUFACTURER") "GENERIC")
        (field (name "AUTHOR") "CERN DEM JLC")
      )
      (libsource (lib "Resistors") (part "Resistor - 1%"))
    )
    (comp (ref "R281")
      (value "4k7")
      (footprint "RESC1005X40N")
      (description "Resistor - 1%")
      (fields
        (field (name "MANUFACTURER PART NUMBER") "R0402_4K7_1%_0.0625W_100PPM")
        (field (name "MANUFACTURER") "GENERIC")
        (field (name "AUTHOR") "CERN DEM JLC")
      )
      (libsource (lib "Resistors") (part "Resistor - 1%"))
    )
    (comp (ref "R282")
      (value "0")
      (footprint "RESC1005X40N")
      (description "Resistor")
      (fields
        (field (name "MANUFACTURER PART NUMBER") "R0402_0R_JUMPER")
        (field (name "MANUFACTURER") "GENERIC")
        (field (name "AUTHOR") "CERN DEM JLC")
      )
      (libsource (lib "Resistors") (part "Resistor"))
    )
    (comp (ref "R293")
      (value "49R9")
      (footprint "RESC1005X40N")
      (description "Resistor - 1%")
      (fields
        (field (name "MANUFACTURER PART NUMBER") "R0402_49R9_1%_0.0625W_100PPM")
        (field (name "MANUFACTURER") "GENERIC")
        (field (name "AUTHOR") "CERN DEM JLC")
      )
      (libsource (lib "Resistors") (part "Resistor - 1%"))
    )
    (comp (ref "R310")
      (value "49R9")
      (footprint "RESC1005X40N")
      (description "Resistor - 1%")
      (fields
        (field (name "MANUFACTURER PART NUMBER") "R0402_49R9_1%_0.0625W_100PPM")
        (field (name "MANUFACTURER") "GENERIC")
        (field (name "AUTHOR") "CERN DEM JLC")
      )
      (libsource (lib "Resistors") (part "Resistor - 1%"))
    )
    (comp (ref "R311")
      (value "0")
      (footprint "RESC1005X40N")
      (description "Resistor")
      (fields
        (field (name "MANUFACTURER PART NUMBER") "R0402_0R_JUMPER")
        (field (name "MANUFACTURER") "GENERIC")
        (field (name "AUTHOR") "CERN DEM JLC")
      )
      (libsource (lib "Resistors") (part "Resistor"))
    )
    (comp (ref "R315")
      (value "150")
      (footprint "RESC1005X40N")
      (description "Resistor - 1%")
      (fields
        (field (name "MANUFACTURER PART NUMBER") "R0402_150R_1%_0.0625W_100PPM")
        (field (name "MANUFACTURER") "GENERIC")
        (field (name "AUTHOR") "CERN DEM JLC")
      )
      (libsource (lib "Resistors") (part "Resistor - 1%"))
    )
    (comp (ref "R316")
      (value "200")
      (footprint "RESC1005X40N")
      (description "Resistor - 1%")
      (fields
        (field (name "MANUFACTURER PART NUMBER") "R0402_200R_1%_0.0625W_100PPM")
        (field (name "MANUFACTURER") "GENERIC")
        (field (name "AUTHOR") "CERN DEM JLC")
      )
      (libsource (lib "Resistors") (part "Resistor - 1%"))
    )
    (comp (ref "R317")
      (value "200")
      (footprint "RESC1005X40N")
      (description "Resistor - 1%")
      (fields
        (field (name "MANUFACTURER PART NUMBER") "R0402_200R_1%_0.0625W_100PPM")
        (field (name "MANUFACTURER") "GENERIC")
        (field (name "AUTHOR") "CERN DEM JLC")
      )
      (libsource (lib "Resistors") (part "Resistor - 1%"))
    )
    (comp (ref "R319")
      (value "0")
      (footprint "RESC1005X40N")
      (description "Resistor")
      (fields
        (field (name "MANUFACTURER PART NUMBER") "R0402_0R_JUMPER")
        (field (name "MANUFACTURER") "GENERIC")
        (field (name "AUTHOR") "CERN DEM JLC")
      )
      (libsource (lib "Resistors") (part "Resistor"))
    )
    (comp (ref "R320")
      (value "0")
      (footprint "RESC1005X40N")
      (description "Resistor")
      (fields
        (field (name "MANUFACTURER PART NUMBER") "R0402_0R_JUMPER")
        (field (name "MANUFACTURER") "GENERIC")
        (field (name "AUTHOR") "CERN DEM JLC")
      )
      (libsource (lib "Resistors") (part "Resistor"))
    )
    (comp (ref "TP1")
      (value "Test Point")
      (footprint "TPS127")
      (fields (field (name "PART NUMBER") "SMD_PAD_1.27X1.27MM") (field (name "AUTHOR") "CERN DEM JLC"))
      (libsource (lib "Eletro-mechanical") (part "Test Point"))
    )
    (comp (ref "TP2")
      (value "Test Point")
      (footprint "TPS127")
      (fields (field (name "PART NUMBER") "SMD_PAD_1.27X1.27MM") (field (name "AUTHOR") "CERN DEM JLC"))
      (libsource (lib "Eletro-mechanical") (part "Test Point"))
    )
    (comp (ref "TP3")
      (value "Test Point")
      (footprint "TPS127")
      (fields (field (name "PART NUMBER") "SMD_PAD_1.27X1.27MM") (field (name "AUTHOR") "CERN DEM JLC"))
      (libsource (lib "Eletro-mechanical") (part "Test Point"))
    )
    (comp (ref "TP4")
      (value "Test Point")
      (footprint "TPS127")
      (fields (field (name "PART NUMBER") "SMD_PAD_1.27X1.27MM") (field (name "AUTHOR") "CERN DEM JLC"))
      (libsource (lib "Eletro-mechanical") (part "Test Point"))
    )
    (comp (ref "TP5")
      (value "Test Point")
      (footprint "TPS127")
      (fields (field (name "PART NUMBER") "SMD_PAD_1.27X1.27MM") (field (name "AUTHOR") "CERN DEM JLC"))
      (libsource (lib "Eletro-mechanical") (part "Test Point"))
    )
    (comp (ref "TP6")
      (value "Test Point")
      (footprint "TPS127")
      (fields (field (name "PART NUMBER") "SMD_PAD_1.27X1.27MM") (field (name "AUTHOR") "CERN DEM JLC"))
      (libsource (lib "Eletro-mechanical") (part "Test Point"))
    )
    (comp (ref "TP14")
      (value "Test Point")
      (footprint "TPS127")
      (fields (field (name "PART NUMBER") "SMD_PAD_1.27X1.27MM") (field (name "AUTHOR") "CERN DEM JLC"))
      (libsource (lib "Eletro-mechanical") (part "Test Point"))
    )
    (comp (ref "TP15")
      (value "Test Point")
      (footprint "TPS127")
      (fields (field (name "PART NUMBER") "SMD_PAD_1.27X1.27MM") (field (name "AUTHOR") "CERN DEM JLC"))
      (libsource (lib "Eletro-mechanical") (part "Test Point"))
    )
    (comp (ref "TR2")
      (value "1:2")
      (footprint "XFMR_MINI-CIRCUITS_DB1627")
      (description "50 OHMS 10 to 4000 MHz RF Transformer")
      (fields
        (field (name "PART NUMBER") "XFMR_MINI-CIRCUITS_TCM2-43X+")
        (field (name "POWER") "0.4W")
        (field (name "MANUFACTURER PART NUMBER") "TCM2-43X+")
        (field (name "AUTHOR") "CERN DEM BC")
      )
      (libsource (lib "Inductors & Transformers") (part "XFMR_MINI-CIRCUITS_TCM2-43X"))
    )
  )
  (nets
    (net (code "4") (name "/AUX_CLOCK_C2_N") (class "Default")
      (node (ref "C108") (pin "2") (pinfunction "2_2") (pintype "passive"))
      (node (ref "R93") (pin "1") (pinfunction "1_1") (pintype "passive"))
    )
    (net (code "5") (name "/AUX_CLOCK_C2_P") (class "Default")
      (node (ref "C107") (pin "2") (pinfunction "2_2") (pintype "passive"))
      (node (ref "R93") (pin "2") (pinfunction "2_2") (pintype "passive"))
    )
    (net (code "6") (name "/CLK_SEL") (class "Default")
      (node (ref "IC20") (pin "32") (pinfunction "IN_SEL_32") (pintype "input"))
    )
    (net (code "7") (name "/Helper_DCXO_OE") (class "Default")
      (node (ref "R311") (pin "2") (pinfunction "2_2") (pintype "passive"))
      (node (ref "R320") (pin "2") (pinfunction "2_2") (pintype "passive"))
    )
    (net (code "8") (name "/Helper_DCXO_SCL") (class "Default")
      (node (ref "OSC4") (pin "8") (pinfunction "SCL_8") (pintype "passive"))
      (node (ref "R281") (pin "1") (pinfunction "1_1") (pintype "passive"))
      (node (ref "TP6") (pin "1") (pinfunction "1_1") (pintype "bidirectional"))
    )
    (net (code "9") (name "/Helper_DCXO_SDA") (class "Default")
      (node (ref "OSC4") (pin "7") (pinfunction "SDA_7") (pintype "passive"))
      (node (ref "R280") (pin "1") (pinfunction "1_1") (pintype "passive"))
      (node (ref "TP5") (pin "1") (pinfunction "1_1") (pintype "bidirectional"))
    )
    (net (code "10") (name "/Main_DCXO_N") (class "Default")
      (node (ref "C533") (pin "2") (pinfunction "2_2") (pintype "passive"))
      (node (ref "C537") (pin "2") (pinfunction "2_2") (pintype "passive"))
      (node (ref "IC20") (pin "2") (pinfunction "~{CLK0}_2") (pintype "input"))
    )
    (net (code "11") (name "/Main_DCXO_OE") (class "Default")
      (node (ref "R263") (pin "2") (pinfunction "2_2") (pintype "passive"))
      (node (ref "R272") (pin "2") (pinfunction "2_2") (pintype "passive"))
    )
    (net (code "12") (name "/Main_DCXO_P") (class "Default")
      (node (ref "C532") (pin "2") (pinfunction "2_2") (pintype "passive"))
      (node (ref "IC20") (pin "1") (pinfunction "CLK0_1") (pintype "input"))
    )
    (net (code "13") (name "/Main_DCXO_SCL") (class "Default")
      (node (ref "OSC3") (pin "8") (pinfunction "SCL_8") (pintype "passive"))
      (node (ref "R260") (pin "1") (pinfunction "1_1") (pintype "passive"))
      (node (ref "TP4") (pin "1") (pinfunction "1_1") (pintype "bidirectional"))
    )
    (net (code "14") (name "/Main_DCXO_SDA") (class "Default")
      (node (ref "OSC3") (pin "7") (pinfunction "SDA_7") (pintype "passive"))
      (node (ref "R259") (pin "1") (pinfunction "1_1") (pintype "passive"))
      (node (ref "TP3") (pin "1") (pinfunction "1_1") (pintype "bidirectional"))
    )
    (net (code "15") (name "/P3V3_CLKDIS4F") (class "Default")
      (node (ref "C542") (pin "1") (pinfunction "1_1") (pintype "passive"))
      (node (ref "C543") (pin "2") (pinfunction "2_2") (pintype "passive"))
      (node (ref "C544") (pin "2") (pinfunction "2_2") (pintype "passive"))
      (node (ref "C545") (pin "2") (pinfunction "2_2") (pintype "passive"))
      (node (ref "C546") (pin "2") (pinfunction "2_2") (pintype "passive"))
      (node (ref "C547") (pin "2") (pinfunction "2_2") (pintype "passive"))
      (node (ref "C548") (pin "2") (pinfunction "2_2") (pintype "passive"))
      (node (ref "IC20") (pin "10") (pinfunction "VCC_10") (pintype "power_in"))
      (node (ref "IC20") (pin "15") (pinfunction "VCC_15") (pintype "power_in"))
      (node (ref "IC20") (pin "16") (pinfunction "VCC_16") (pintype "power_in"))
      (node (ref "IC20") (pin "25") (pinfunction "VCC_25") (pintype "power_in"))
      (node (ref "IC20") (pin "26") (pinfunction "VCC_26") (pintype "power_in"))
      (node (ref "IC20") (pin "31") (pinfunction "VCC_31") (pintype "power_in"))
      (node (ref "L16") (pin "2") (pinfunction "2_2") (pintype "passive"))
    )
    (net (code "16") (name "/P5V0_LDO_IN") (class "Default")
      (node (ref "C515") (pin "2") (pinfunction "2_2") (pintype "passive"))
      (node (ref "IC17") (pin "1") (pinfunction "EN_1") (pintype "power_in"))
      (node (ref "IC17") (pin "2") (pinfunction "IN_2") (pintype "input"))
      (node (ref "L4") (pin "2") (pinfunction "2_2") (pintype "passive"))
    )
    (net (code "17") (name "/REC_CLOCK_C_N") (class "Default")
      (node (ref "84") (pin "1") (pinfunction "1_1") (pintype "passive"))
      (node (ref "C99") (pin "2") (pinfunction "2_2") (pintype "passive"))
    )
    (net (code "18") (name "/REC_CLOCK_C_P") (class "Default")
      (node (ref "84") (pin "2") (pinfunction "2_2") (pintype "passive"))
      (node (ref "C98") (pin "2") (pinfunction "2_2") (pintype "passive"))
    )
    (net (code "19") (name "/REC_CLOCK_N") (class "Default")
      (node (ref "C99") (pin "1") (pinfunction "1_1") (pintype "passive"))
      (node (ref "IC18") (pin "17") (pinfunction "CKIN1-_17") (pintype "input"))
    )
    (net (code "20") (name "/REC_CLOCK_P") (class "Default")
      (node (ref "C98") (pin "1") (pinfunction "1_1") (pintype "passive"))
      (node (ref "IC18") (pin "16") (pinfunction "CKIN1+_16") (pintype "input"))
    )
    (net (code "21") (name "/REF_LOC_N") (class "Default")
      (node (ref "C110") (pin "2") (pinfunction "2_2") (pintype "passive"))
      (node (ref "IC20") (pin "6") (pinfunction "~{CLK1}_6") (pintype "input"))
    )
    (net (code "22") (name "/REF_LOC_P") (class "Default")
      (node (ref "C109") (pin "2") (pinfunction "2_2") (pintype "passive"))
      (node (ref "IC20") (pin "5") (pinfunction "CLK1_5") (pintype "input"))
    )
    (net (code "23") (name "/SI5324_INT_ALM") (class "Default")
      (node (ref "IC18") (pin "3") (pinfunction "INT_C1B_3") (pintype "output"))
    )
    (net (code "24") (name "/SI5324_RST") (class "Default")
      (node (ref "IC18") (pin "1") (pinfunction "~{RST}_1") (pintype "input"))
    )
    (net (code "25") (name "/SI5324_SCL") (class "Default")
      (node (ref "IC18") (pin "22") (pinfunction "SCL_22") (pintype "input"))
      (node (ref "TP2") (pin "1") (pinfunction "1_1") (pintype "bidirectional"))
    )
    (net (code "26") (name "/SI5324_SDA") (class "Default")
      (node (ref "IC18") (pin "23") (pinfunction "SDA_SDO_23") (pintype "bidirectional"))
      (node (ref "TP1") (pin "1") (pinfunction "1_1") (pintype "bidirectional"))
    )
    (net (code "27") (name "/SI5324_VDD") (class "Default")
      (node (ref "C111") (pin "2") (pinfunction "2_2") (pintype "passive"))
      (node (ref "C355") (pin "1") (pinfunction "1_1") (pintype "passive"))
      (node (ref "C96") (pin "2") (pinfunction "2_2") (pintype "passive"))
      (node (ref "C97") (pin "2") (pinfunction "2_2") (pintype "passive"))
      (node (ref "IC18") (pin "10") (pinfunction "VDD_10") (pintype "power_in"))
      (node (ref "IC18") (pin "32") (pinfunction "VDD_32") (pintype "power_in"))
      (node (ref "IC18") (pin "5") (pinfunction "VDD_5") (pintype "power_in"))
      (node (ref "L12") (pin "2") (pinfunction "2_2") (pintype "passive"))
    )
    (net (code "28") (name "/SI5324_XTAL_XA") (class "Default")
      (node (ref "IC18") (pin "6") (pinfunction "XA_6") (pintype "input"))
      (node (ref "Q1") (pin "3") (pinfunction "X_3") (pintype "passive"))
    )
    (net (code "29") (name "/SI5324_XTAL_XB") (class "Default")
      (node (ref "IC18") (pin "7") (pinfunction "XB_7") (pintype "input"))
      (node (ref "Q1") (pin "1") (pinfunction "X_1") (pintype "passive"))
    )
    (net (code "33") (name "GND") (class "Default")
      (node (ref "85") (pin "1") (pinfunction "1_1") (pintype "passive"))
      (node (ref "C111") (pin "1") (pinfunction "1_1") (pintype "passive"))
      (node (ref "C324") (pin "1") (pinfunction "1_1") (pintype "passive"))
      (node (ref "C355") (pin "2") (pinfunction "2_2") (pintype "passive"))
      (node (ref "C356") (pin "1") (pinfunction "1_1") (pintype "passive"))
      (node (ref "C430") (pin "1") (pinfunction "1_1") (pintype "passive"))
      (node (ref "C431") (pin "1") (pinfunction "1_1") (pintype "passive"))
      (node (ref "C513") (pin "1") (pinfunction "1_1") (pintype "passive"))
      (node (ref "C514") (pin "1") (pinfunction "1_1") (pintype "passive"))
      (node (ref "C515") (pin "1") (pinfunction "1_1") (pintype "passive"))
      (node (ref "C518") (pin "1") (pinfunction "1_1") (pintype "passive"))
      (node (ref "C536") (pin "1") (pinfunction "1_1") (pintype "passive"))
      (node (ref "C537") (pin "1") (pinfunction "1_1") (pintype "passive"))
      (node (ref "C539") (pin "1") (pinfunction "1_1") (pintype "passive"))
      (node (ref "C542") (pin "2") (pinfunction "2_2") (pintype "passive"))
      (node (ref "C543") (pin "1") (pinfunction "1_1") (pintype "passive"))
      (node (ref "C544") (pin "1") (pinfunction "1_1") (pintype "passive"))
      (node (ref "C545") (pin "1") (pinfunction "1_1") (pintype "passive"))
      (node (ref "C546") (pin "1") (pinfunction "1_1") (pintype "passive"))
      (node (ref "C547") (pin "1") (pinfunction "1_1") (pintype "passive"))
      (node (ref "C548") (pin "1") (pinfunction "1_1") (pintype "passive"))
      (node (ref "C550") (pin "1") (pinfunction "1_1") (pintype "passive"))
      (node (ref "C551") (pin "1") (pinfunction "1_1") (pintype "passive"))
      (node (ref "C555") (pin "1") (pinfunction "1_1") (pintype "passive"))
      (node (ref "C96") (pin "1") (pinfunction "1_1") (pintype "passive"))
      (node (ref "C97") (pin "1") (pinfunction "1_1") (pintype "passive"))
      (node (ref "IC17") (pin "3") (pinfunction "GND_3") (pintype "power_in"))
      (node (ref "IC17") (pin "6") (pinfunction "GND_6") (pintype "power_in"))
      (node (ref "IC18") (pin "19") (pinfunction "GND_19") (pintype "power_in"))
      (node (ref "IC18") (pin "20") (pinfunction "GND_20") (pintype "power_in"))
      (node (ref "IC18") (pin "24") (pinfunction "A0_24") (pintype "input"))
      (node (ref "IC18") (pin "25") (pinfunction "A1_25") (pintype "input"))
      (node (ref "IC18") (pin "26") (pinfunction "A2_~{SS}_26") (pintype "input"))
      (node (ref "IC18") (pin "31") (pinfunction "GND_31") (pintype "power_in"))
      (node (ref "IC18") (pin "36") (pinfunction "CMODE_36") (pintype "input"))
      (node (ref "IC18") (pin "37") (pinfunction "GND_37") (pintype "power_in"))
      (node (ref "IC18") (pin "8") (pinfunction "GND_8") (pintype "power_in"))
      (node (ref "IC20") (pin "33") (pinfunction "VEE_33") (pintype "power_in"))
      (node (ref "J10") (pin "2") (pinfunction "2_2") (pintype "bidirectional"))
      (node (ref "J16") (pin "2") (pinfunction "2_2") (pintype "bidirectional"))
      (node (ref "J17") (pin "2") (pinfunction "2_2") (pintype "bidirectional"))
      (node (ref "J24") (pin "2") (pinfunction "2_2") (pintype "bidirectional"))
      (node (ref "OSC3") (pin "3") (pinfunction "GND_3") (pintype "passive"))
      (node (ref "OSC4") (pin "3") (pinfunction "GND_3") (pintype "passive"))
      (node (ref "Q1") (pin "2") (pinfunction "GND_2") (pintype "power_in"))
      (node (ref "Q1") (pin "4") (pinfunction "GND_4") (pintype "power_in"))
      (node (ref "R145") (pin "1") (pinfunction "1_1") (pintype "passive"))
      (node (ref "R147") (pin "2") (pinfunction "2_2") (pintype "passive"))
      (node (ref "R149") (pin "2") (pinfunction "2_2") (pintype "passive"))
      (node (ref "R151") (pin "2") (pinfunction "2_2") (pintype "passive"))
      (node (ref "R153") (pin "2") (pinfunction "2_2") (pintype "passive"))
      (node (ref "R261") (pin "2") (pinfunction "2_2") (pintype "passive"))
      (node (ref "R265") (pin "2") (pinfunction "2_2") (pintype "passive"))
      (node (ref "R268") (pin "1") (pinfunction "1_1") (pintype "passive"))
      (node (ref "R269") (pin "1") (pinfunction "1_1") (pintype "passive"))
      (node (ref "R270") (pin "2") (pinfunction "2_2") (pintype "passive"))
      (node (ref "R273") (pin "2") (pinfunction "2_2") (pintype "passive"))
      (node (ref "R277") (pin "2") (pinfunction "2_2") (pintype "passive"))
      (node (ref "R278") (pin "2") (pinfunction "2_2") (pintype "passive"))
      (node (ref "R316") (pin "1") (pinfunction "1_1") (pintype "passive"))
      (node (ref "R317") (pin "1") (pinfunction "1_1") (pintype "passive"))
      (node (ref "R319") (pin "1") (pinfunction "1_1") (pintype "passive"))
      (node (ref "TR2") (pin "1") (pinfunction "P1_1") (pintype "passive"))
      (node (ref "TR2") (pin "2") (pinfunction "P1_2") (pintype "passive"))
      (node (ref "TR2") (pin "5") (pinfunction "NC_5") (pintype "passive"))
    )
    (net (code "34") (name "Net-(C328-Pad1)") (class "Default")
      (node (ref "C328") (pin "1") (pinfunction "1_1") (pintype "passive"))
      (node (ref "J10") (pin "1") (pinfunction "1_1") (pintype "bidirectional"))
    )
    (net (code "35") (name "Net-(C328-Pad2)") (class "Default")
      (node (ref "C328") (pin "2") (pinfunction "2_2") (pintype "passive"))
      (node (ref "R144") (pin "2") (pinfunction "2_2") (pintype "passive"))
      (node (ref "TR2") (pin "3") (pinfunction "P1_3") (pintype "passive"))
    )
    (net (code "36") (name "Net-(C329-Pad1)") (class "Default")
      (node (ref "C329") (pin "1") (pinfunction "1_1") (pintype "passive"))
      (node (ref "R144") (pin "1") (pinfunction "1_1") (pintype "passive"))
      (node (ref "TR2") (pin "6") (pinfunction "S1_6") (pintype "passive"))
    )
    (net (code "37") (name "Net-(C332-Pad1)") (class "Default")
      (node (ref "C332") (pin "1") (pinfunction "1_1") (pintype "passive"))
      (node (ref "R145") (pin "2") (pinfunction "2_2") (pintype "passive"))
      (node (ref "TR2") (pin "4") (pinfunction "S1_4") (pintype "passive"))
    )
    (net (code "38") (name "Net-(C356-Pad2)") (class "Default")
      (node (ref "C356") (pin "2") (pinfunction "2_2") (pintype "passive"))
      (node (ref "R146") (pin "2") (pinfunction "2_2") (pintype "passive"))
      (node (ref "R259") (pin "2") (pinfunction "2_2") (pintype "passive"))
      (node (ref "R260") (pin "2") (pinfunction "2_2") (pintype "passive"))
      (node (ref "R280") (pin "2") (pinfunction "2_2") (pintype "passive"))
      (node (ref "R281") (pin "2") (pinfunction "2_2") (pintype "passive"))
    )
    (net (code "39") (name "Net-(C359-Pad1)") (class "Default")
      (node (ref "C359") (pin "1") (pinfunction "1_1") (pintype "passive"))
      (node (ref "R148") (pin "2") (pinfunction "2_2") (pintype "passive"))
    )
    (net (code "40") (name "Net-(C360-Pad1)") (class "Default")
      (node (ref "C360") (pin "1") (pinfunction "1_1") (pintype "passive"))
      (node (ref "R150") (pin "2") (pinfunction "2_2") (pintype "passive"))
    )
    (net (code "41") (name "Net-(C445-Pad1)") (class "Default")
      (node (ref "C445") (pin "1") (pinfunction "1_1") (pintype "passive"))
      (node (ref "R152") (pin "2") (pinfunction "2_2") (pintype "passive"))
    )
    (net (code "42") (name "Net-(C446-Pad1)") (class "Default")
      (node (ref "C446") (pin "1") (pinfunction "1_1") (pintype "passive"))
      (node (ref "R154") (pin "2") (pinfunction "2_2") (pintype "passive"))
    )
    (net (code "43") (name "Net-(C532-Pad1)") (class "Default")
      (node (ref "C532") (pin "1") (pinfunction "1_1") (pintype "passive"))
      (node (ref "R264") (pin "1") (pinfunction "1_1") (pintype "passive"))
      (node (ref "R268") (pin "2") (pinfunction "2_2") (pintype "passive"))
    )
    (net (code "44") (name "Net-(C534-Pad1)") (class "Default")
      (node (ref "C534") (pin "1") (pinfunction "1_1") (pintype "passive"))
      (node (ref "R262") (pin "2") (pinfunction "2_2") (pintype "passive"))
    )
    (net (code "45") (name "Net-(C535-Pad1)") (class "Default")
      (node (ref "C535") (pin "1") (pinfunction "1_1") (pintype "passive"))
      (node (ref "R266") (pin "2") (pinfunction "2_2") (pintype "passive"))
    )
    (net (code "46") (name "Net-(C540-Pad1)") (class "Default")
      (node (ref "C540") (pin "1") (pinfunction "1_1") (pintype "passive"))
      (node (ref "R271") (pin "2") (pinfunction "2_2") (pintype "passive"))
    )
    (net (code "47") (name "Net-(C541-Pad1)") (class "Default")
      (node (ref "C541") (pin "1") (pinfunction "1_1") (pintype "passive"))
      (node (ref "R276") (pin "2") (pinfunction "2_2") (pintype "passive"))
    )
    (net (code "48") (name "Net-(C549-Pad2)") (class "Default")
      (node (ref "C549") (pin "2") (pinfunction "2_2") (pintype "passive"))
      (node (ref "J17") (pin "1") (pinfunction "1_1") (pintype "bidirectional"))
    )
    (net (code "49") (name "Net-(C552-Pad2)") (class "Default")
      (node (ref "C552") (pin "2") (pinfunction "2_2") (pintype "passive"))
      (node (ref "J24") (pin "1") (pinfunction "1_1") (pintype "bidirectional"))
    )
    (net (code "50") (name "Net-(C553-Pad1)") (class "Default")
      (node (ref "C553") (pin "1") (pinfunction "1_1") (pintype "passive"))
      (node (ref "R282") (pin "2") (pinfunction "2_2") (pintype "passive"))
      (node (ref "R315") (pin "1") (pinfunction "1_1") (pintype "passive"))
      (node (ref "R316") (pin "2") (pinfunction "2_2") (pintype "passive"))
    )
    (net (code "51") (name "Net-(C553-Pad2)") (class "Default")
      (node (ref "C553") (pin "2") (pinfunction "2_2") (pintype "passive"))
      (node (ref "R279") (pin "2") (pinfunction "2_2") (pintype "passive"))
      (node (ref "R282") (pin "1") (pinfunction "1_1") (pintype "passive"))
      (node (ref "R293") (pin "1") (pinfunction "1_1") (pintype "passive"))
    )
    (net (code "52") (name "Net-(C554-Pad2)") (class "Default")
      (node (ref "C554") (pin "2") (pinfunction "2_2") (pintype "passive"))
      (node (ref "R310") (pin "1") (pinfunction "1_1") (pintype "passive"))
      (node (ref "R319") (pin "2") (pinfunction "2_2") (pintype "passive"))
    )
    (net (code "53") (name "Net-(IC17-NR)") (class "Default")
      (node (ref "C324") (pin "2") (pinfunction "2_2") (pintype "passive"))
      (node (ref "IC17") (pin "5") (pinfunction "NR_5") (pintype "passive"))
    )
    (net (code "54") (name "Net-(IC18-CKIN2+)") (class "Default")
      (node (ref "C107") (pin "1") (pinfunction "1_1") (pintype "passive"))
      (node (ref "IC18") (pin "12") (pinfunction "CKIN2+_12") (pintype "input"))
    )
    (net (code "55") (name "Net-(IC18-CKIN2-)") (class "Default")
      (node (ref "C108") (pin "1") (pinfunction "1_1") (pintype "passive"))
      (node (ref "IC18") (pin "13") (pinfunction "CKIN2-_13") (pintype "input"))
    )
    (net (code "56") (name "Net-(IC18-CKOUT2+)") (class "Default")
      (node (ref "C109") (pin "1") (pinfunction "1_1") (pintype "passive"))
      (node (ref "IC18") (pin "35") (pinfunction "CKOUT2+_35") (pintype "output"))
      (node (ref "TP14") (pin "1") (pinfunction "1_1") (pintype "bidirectional"))
    )
    (net (code "57") (name "Net-(IC18-CKOUT2-)") (class "Default")
      (node (ref "C110") (pin "1") (pinfunction "1_1") (pintype "passive"))
      (node (ref "IC18") (pin "34") (pinfunction "CKOUT2-_34") (pintype "output"))
      (node (ref "TP15") (pin "1") (pinfunction "1_1") (pintype "bidirectional"))
    )
    (net (code "58") (name "Net-(IC18-CS_CA)") (class "Default")
      (node (ref "85") (pin "2") (pinfunction "2_2") (pintype "passive"))
      (node (ref "IC18") (pin "21") (pinfunction "CS_CA_21") (pintype "bidirectional"))
    )
    (net (code "59") (name "Net-(IC20-Q0)") (class "Default")
      (node (ref "IC20") (pin "30") (pinfunction "Q0_30") (pintype "output"))
      (node (ref "R147") (pin "1") (pinfunction "1_1") (pintype "passive"))
      (node (ref "R148") (pin "1") (pinfunction "1_1") (pintype "passive"))
    )
    (net (code "60") (name "Net-(IC20-Q1)") (class "Default")
      (node (ref "IC20") (pin "28") (pinfunction "Q1_28") (pintype "output"))
      (node (ref "R151") (pin "1") (pinfunction "1_1") (pintype "passive"))
      (node (ref "R152") (pin "1") (pinfunction "1_1") (pintype "passive"))
    )
    (net (code "61") (name "Net-(IC20-Q3)") (class "Default")
      (node (ref "IC20") (pin "22") (pinfunction "Q3_22") (pintype "output"))
      (node (ref "R261") (pin "1") (pinfunction "1_1") (pintype "passive"))
      (node (ref "R262") (pin "1") (pinfunction "1_1") (pintype "passive"))
    )
    (net (code "62") (name "Net-(IC20-Q5)") (class "Default")
      (node (ref "IC20") (pin "18") (pinfunction "Q5_18") (pintype "output"))
      (node (ref "R270") (pin "1") (pinfunction "1_1") (pintype "passive"))
      (node (ref "R271") (pin "1") (pinfunction "1_1") (pintype "passive"))
    )
    (net (code "63") (name "Net-(IC20-Q7)") (class "Default")
      (node (ref "C552") (pin "1") (pinfunction "1_1") (pintype "passive"))
      (node (ref "IC20") (pin "12") (pinfunction "Q7_12") (pintype "output"))
      (node (ref "R277") (pin "1") (pinfunction "1_1") (pintype "passive"))
    )
    (net (code "64") (name "Net-(IC20-VREF0)") (class "Default")
      (node (ref "IC20") (pin "3") (pinfunction "VREF0_3") (pintype "input"))
      (node (ref "R258") (pin "2") (pinfunction "2_2") (pintype "passive"))
    )
    (net (code "65") (name "Net-(IC20-VREF1)") (class "Default")
      (node (ref "IC20") (pin "8") (pinfunction "VREF1_8") (pintype "input"))
      (node (ref "R267") (pin "2") (pinfunction "2_2") (pintype "passive"))
    )
    (net (code "66") (name "Net-(IC20-VT0)") (class "Default")
      (node (ref "C518") (pin "2") (pinfunction "2_2") (pintype "passive"))
      (node (ref "IC20") (pin "4") (pinfunction "VT0_4") (pintype "passive"))
      (node (ref "R258") (pin "1") (pinfunction "1_1") (pintype "passive"))
    )
    (net (code "67") (name "Net-(IC20-VT1)") (class "Default")
      (node (ref "C536") (pin "2") (pinfunction "2_2") (pintype "passive"))
      (node (ref "IC20") (pin "7") (pinfunction "VT1_7") (pintype "passive"))
      (node (ref "R267") (pin "1") (pinfunction "1_1") (pintype "passive"))
    )
    (net (code "68") (name "Net-(IC20-~{Q0})") (class "Default")
      (node (ref "IC20") (pin "29") (pinfunction "~{Q0}_29") (pintype "output"))
      (node (ref "R149") (pin "1") (pinfunction "1_1") (pintype "passive"))
      (node (ref "R150") (pin "1") (pinfunction "1_1") (pintype "passive"))
    )
    (net (code "69") (name "Net-(IC20-~{Q1})") (class "Default")
      (node (ref "IC20") (pin "27") (pinfunction "~{Q1}_27") (pintype "output"))
      (node (ref "R153") (pin "1") (pinfunction "1_1") (pintype "passive"))
      (node (ref "R154") (pin "1") (pinfunction "1_1") (pintype "passive"))
    )
    (net (code "70") (name "Net-(IC20-~{Q3})") (class "Default")
      (node (ref "IC20") (pin "21") (pinfunction "~{Q3}_21") (pintype "output"))
      (node (ref "R265") (pin "1") (pinfunction "1_1") (pintype "passive"))
      (node (ref "R266") (pin "1") (pinfunction "1_1") (pintype "passive"))
    )
    (net (code "71") (name "Net-(IC20-~{Q5})") (class "Default")
      (node (ref "IC20") (pin "17") (pinfunction "~{Q5}_17") (pintype "output"))
      (node (ref "R273") (pin "1") (pinfunction "1_1") (pintype "passive"))
      (node (ref "R276") (pin "1") (pinfunction "1_1") (pintype "passive"))
    )
    (net (code "72") (name "Net-(IC20-~{Q7})") (class "Default")
      (node (ref "C549") (pin "1") (pinfunction "1_1") (pintype "passive"))
      (node (ref "IC20") (pin "11") (pinfunction "~{Q7}_11") (pintype "output"))
      (node (ref "R278") (pin "1") (pinfunction "1_1") (pintype "passive"))
    )
    (net (code "73") (name "Net-(J16-Pad1)") (class "Default")
      (node (ref "J16") (pin "1") (pinfunction "1_1") (pintype "bidirectional"))
      (node (ref "R279") (pin "1") (pinfunction "1_1") (pintype "passive"))
    )
    (net (code "74") (name "Net-(OSC3-CLK+)") (class "Default")
      (node (ref "OSC3") (pin "4") (pinfunction "CLK+_4") (pintype "passive"))
      (node (ref "R264") (pin "2") (pinfunction "2_2") (pintype "passive"))
    )
    (net (code "75") (name "Net-(OSC3-CLK-)") (class "Default")
      (node (ref "C533") (pin "1") (pinfunction "1_1") (pintype "passive"))
      (node (ref "OSC3") (pin "5") (pinfunction "CLK-_5") (pintype "passive"))
      (node (ref "R269") (pin "2") (pinfunction "2_2") (pintype "passive"))
    )
    (net (code "76") (name "Net-(OSC3-NC)") (class "Default")
      (node (ref "OSC3") (pin "2") (pinfunction "NC_2") (pintype "passive"))
      (node (ref "R272") (pin "1") (pinfunction "1_1") (pintype "passive"))
    )
    (net (code "77") (name "Net-(OSC3-OE)") (class "Default")
      (node (ref "OSC3") (pin "1") (pinfunction "OE_1") (pintype "passive"))
      (node (ref "R263") (pin "1") (pinfunction "1_1") (pintype "passive"))
    )
    (net (code "78") (name "Net-(OSC3-VDD)") (class "Default")
      (node (ref "C430") (pin "2") (pinfunction "2_2") (pintype "passive"))
      (node (ref "C431") (pin "2") (pinfunction "2_2") (pintype "passive"))
      (node (ref "C539") (pin "2") (pinfunction "2_2") (pintype "passive"))
      (node (ref "L13") (pin "2") (pinfunction "2_2") (pintype "passive"))
      (node (ref "OSC3") (pin "6") (pinfunction "VDD_6") (pintype "passive"))
    )
    (net (code "79") (name "Net-(OSC4-CLK+)") (class "Default")
      (node (ref "OSC4") (pin "4") (pinfunction "CLK+_4") (pintype "passive"))
      (node (ref "R315") (pin "2") (pinfunction "2_2") (pintype "passive"))
    )
    (net (code "80") (name "Net-(OSC4-CLK-)") (class "Default")
      (node (ref "C554") (pin "1") (pinfunction "1_1") (pintype "passive"))
      (node (ref "OSC4") (pin "5") (pinfunction "CLK-_5") (pintype "passive"))
      (node (ref "R317") (pin "2") (pinfunction "2_2") (pintype "passive"))
    )
    (net (code "81") (name "Net-(OSC4-NC)") (class "Default")
      (node (ref "OSC4") (pin "2") (pinfunction "NC_2") (pintype "passive"))
      (node (ref "R320") (pin "1") (pinfunction "1_1") (pintype "passive"))
    )
    (net (code "82") (name "Net-(OSC4-OE)") (class "Default")
      (node (ref "OSC4") (pin "1") (pinfunction "OE_1") (pintype "passive"))
      (node (ref "R311") (pin "1") (pinfunction "1_1") (pintype "passive"))
    )
    (net (code "83") (name "Net-(OSC4-VDD)") (class "Default")
      (node (ref "C550") (pin "2") (pinfunction "2_2") (pintype "passive"))
      (node (ref "C551") (pin "2") (pinfunction "2_2") (pintype "passive"))
      (node (ref "C555") (pin "2") (pinfunction "2_2") (pintype "passive"))
      (node (ref "L21") (pin "2") (pinfunction "2_2") (pintype "passive"))
      (node (ref "OSC4") (pin "6") (pinfunction "VDD_6") (pintype "passive"))
    )
    (net (code "84") (name "P3V3") (class "Default")
      (node (ref "R146") (pin "1") (pinfunction "1_1") (pintype "passive"))
    )
    (net (code "85") (name "P3V3_CLK") (class "Default")
      (node (ref "C513") (pin "2") (pinfunction "2_2") (pintype "passive"))
      (node (ref "C514") (pin "2") (pinfunction "2_2") (pintype "passive"))
      (node (ref "IC17") (pin "4") (pinfunction "OUT_4") (pintype "power_in"))
      (node (ref "L12") (pin "1") (pinfunction "1_1") (pintype "passive"))
      (node (ref "L13") (pin "1") (pinfunction "1_1") (pintype "passive"))
      (node (ref "L16") (pin "1") (pinfunction "1_1") (pintype "passive"))
      (node (ref "L21") (pin "1") (pinfunction "1_1") (pintype "passive"))
    )
    (net (code "86") (name "P5V0") (class "Default")
      (node (ref "L4") (pin "1") (pinfunction "1_1") (pintype "passive"))
    )
    (net (code "87") (name "unconnected-(C329-Pad2)") (class "Default")
      (node (ref "C329") (pin "2") (pinfunction "2_2") (pintype "passive"))
    )
    (net (code "88") (name "unconnected-(C332-Pad2)") (class "Default")
      (node (ref "C332") (pin "2") (pinfunction "2_2") (pintype "passive"))
    )
    (net (code "89") (name "unconnected-(C359-Pad2)") (class "Default")
      (node (ref "C359") (pin "2") (pinfunction "2_2") (pintype "passive"))
    )
    (net (code "90") (name "unconnected-(C360-Pad2)") (class "Default")
      (node (ref "C360") (pin "2") (pinfunction "2_2") (pintype "passive"))
    )
    (net (code "91") (name "unconnected-(C445-Pad2)") (class "Default")
      (node (ref "C445") (pin "2") (pinfunction "2_2") (pintype "passive"))
    )
    (net (code "92") (name "unconnected-(C446-Pad2)") (class "Default")
      (node (ref "C446") (pin "2") (pinfunction "2_2") (pintype "passive"))
    )
    (net (code "93") (name "unconnected-(C534-Pad2)") (class "Default")
      (node (ref "C534") (pin "2") (pinfunction "2_2") (pintype "passive"))
    )
    (net (code "94") (name "unconnected-(C535-Pad2)") (class "Default")
      (node (ref "C535") (pin "2") (pinfunction "2_2") (pintype "passive"))
    )
    (net (code "95") (name "unconnected-(C540-Pad2)") (class "Default")
      (node (ref "C540") (pin "2") (pinfunction "2_2") (pintype "passive"))
    )
    (net (code "96") (name "unconnected-(C541-Pad2)") (class "Default")
      (node (ref "C541") (pin "2") (pinfunction "2_2") (pintype "passive"))
    )
    (net (code "97") (name "unconnected-(IC18-C2B-Pad4)") (class "Default")
      (node (ref "IC18") (pin "4") (pinfunction "C2B_4") (pintype "output+no_connect"))
    )
    (net (code "98") (name "unconnected-(IC18-CKOUT1+-Pad28)") (class "Default")
      (node (ref "IC18") (pin "28") (pinfunction "CKOUT1+_28") (pintype "output+no_connect"))
    )
    (net (code "99") (name "unconnected-(IC18-CKOUT1--Pad29)") (class "Default")
      (node (ref "IC18") (pin "29") (pinfunction "CKOUT1-_29") (pintype "output+no_connect"))
    )
    (net (code "100") (name "unconnected-(IC18-LOL-Pad18)") (class "Default")
      (node (ref "IC18") (pin "18") (pinfunction "LOL_18") (pintype "output+no_connect"))
    )
    (net (code "101") (name "unconnected-(IC18-NC-Pad2)") (class "Default")
      (node (ref "IC18") (pin "2") (pinfunction "NC_2") (pintype "passive+no_connect"))
    )
    (net (code "102") (name "unconnected-(IC18-NC-Pad9)") (class "Default")
      (node (ref "IC18") (pin "9") (pinfunction "NC_9") (pintype "passive+no_connect"))
    )
    (net (code "103") (name "unconnected-(IC18-NC-Pad14)") (class "Default")
      (node (ref "IC18") (pin "14") (pinfunction "NC_14") (pintype "passive+no_connect"))
    )
    (net (code "104") (name "unconnected-(IC18-NC-Pad30)") (class "Default")
      (node (ref "IC18") (pin "30") (pinfunction "NC_30") (pintype "passive+no_connect"))
    )
    (net (code "105") (name "unconnected-(IC18-NC-Pad33)") (class "Default")
      (node (ref "IC18") (pin "33") (pinfunction "NC_33") (pintype "passive+no_connect"))
    )
    (net (code "106") (name "unconnected-(IC18-RATE0-Pad11)") (class "Default")
      (node (ref "IC18") (pin "11") (pinfunction "RATE0_11") (pintype "input+no_connect"))
    )
    (net (code "107") (name "unconnected-(IC18-RATE1-Pad15)") (class "Default")
      (node (ref "IC18") (pin "15") (pinfunction "RATE1_15") (pintype "input+no_connect"))
    )
    (net (code "108") (name "unconnected-(IC18-SDI-Pad27)") (class "Default")
      (node (ref "IC18") (pin "27") (pinfunction "SDI_27") (pintype "input+no_connect"))
    )
    (net (code "109") (name "unconnected-(IC20-NC-Pad9)") (class "Default")
      (node (ref "IC20") (pin "9") (pinfunction "NC_9") (pintype "passive+no_connect"))
    )
    (net (code "110") (name "unconnected-(IC20-Q2-Pad24)") (class "Default")
      (node (ref "IC20") (pin "24") (pinfunction "Q2_24") (pintype "output"))
    )
    (net (code "111") (name "unconnected-(IC20-Q4-Pad20)") (class "Default")
      (node (ref "IC20") (pin "20") (pinfunction "Q4_20") (pintype "output"))
    )
    (net (code "112") (name "unconnected-(IC20-Q6-Pad14)") (class "Default")
      (node (ref "IC20") (pin "14") (pinfunction "Q6_14") (pintype "output+no_connect"))
    )
    (net (code "113") (name "unconnected-(IC20-~{Q2}-Pad23)") (class "Default")
      (node (ref "IC20") (pin "23") (pinfunction "~{Q2}_23") (pintype "output"))
    )
    (net (code "114") (name "unconnected-(IC20-~{Q4}-Pad19)") (class "Default")
      (node (ref "IC20") (pin "19") (pinfunction "~{Q4}_19") (pintype "output"))
    )
    (net (code "115") (name "unconnected-(IC20-~{Q6}-Pad13)") (class "Default")
      (node (ref "IC20") (pin "13") (pinfunction "~{Q6}_13") (pintype "output+no_connect"))
    )
    (net (code "116") (name "unconnected-(R293-Pad2)") (class "Default")
      (node (ref "R293") (pin "2") (pinfunction "2_2") (pintype "passive"))
    )
    (net (code "117") (name "unconnected-(R310-Pad2)") (class "Default")
      (node (ref "R310") (pin "2") (pinfunction "2_2") (pintype "passive"))
    )
  )
)
